# zap.net
KiCad netlist of a schematic drawn in EAGLE
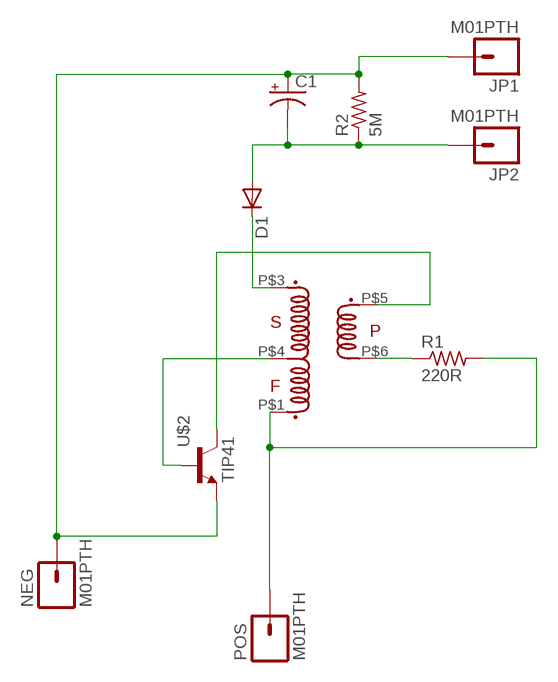
[diagram p0: schematic, sheet 1]

(export (version "E")
  (design (tool "Eeschema 10.0.6"))
  (components
    (comp (ref "C1")
      (value "CAPACITOR_POL")
      (footprint "eagle-import:E5-10,5-SIDE")
      (libsource (lib "eagle-import") (part "CAPACITOR_POL"))
    )
    (comp (ref "D1")
      (value "DIODEPTH")
      (footprint "eagle-import:DIODE-1N4001")
      (libsource (lib "eagle-import") (part "DIODEPTH"))
    )
    (comp (ref "JP1")
      (value "M01PTH")
      (footprint "eagle-import:1X01")
      (libsource (lib "eagle-import") (part "M01PTH"))
    )
    (comp (ref "JP2")
      (value "M01PTH")
      (footprint "eagle-import:1X01")
      (libsource (lib "eagle-import") (part "M01PTH"))
    )
    (comp (ref "NEG")
      (value "M01PTH")
      (footprint "eagle-import:1X01")
      (libsource (lib "eagle-import") (part "M01PTH"))
    )
    (comp (ref "POS")
      (value "M01PTH")
      (footprint "eagle-import:1X01")
      (libsource (lib "eagle-import") (part "M01PTH"))
    )
    (comp (ref "R1")
      (value "220R")
      (footprint "eagle-import:0207_12")
      (libsource (lib "eagle-import") (part "RESISTOR0207/12"))
    )
    (comp (ref "R2")
      (value "5M")
      (footprint "eagle-import:0207_7")
      (libsource (lib "eagle-import") (part "RESISTOR0207/7"))
    )
    (comp (ref "U$1")
      (value "XFT-FLYBACK3V")
      (footprint "eagle-import:XFT-FLYBACK")
      (libsource (lib "eagle-import") (part "XFT-FLYBACK3V"))
    )
    (comp (ref "U$2")
      (value "TIP41")
      (footprint "eagle-import:TO220H")
      (libsource (lib "eagle-import") (part "TIP41"))
    )
  )
  (nets
    (net (code "1") (name "Net-(C1-+)") (class "Default")
      (node (ref "C1") (pin "P$1") (pinfunction "+_P$1") (pintype "passive"))
      (node (ref "JP1") (pin "1") (pinfunction "1_1") (pintype "passive"))
      (node (ref "NEG") (pin "1") (pinfunction "1_1") (pintype "passive"))
      (node (ref "R2") (pin "2") (pinfunction "2_2") (pintype "passive"))
      (node (ref "U$2") (pin "3") (pinfunction "E_3") (pintype "passive"))
    )
    (net (code "2") (name "Net-(C1--)") (class "Default")
      (node (ref "C1") (pin "P$2") (pinfunction "-_P$2") (pintype "passive"))
      (node (ref "D1") (pin "A") (pinfunction "A_A") (pintype "passive"))
      (node (ref "JP2") (pin "1") (pinfunction "1_1") (pintype "passive"))
      (node (ref "R2") (pin "1") (pinfunction "1_1") (pintype "passive"))
    )
    (net (code "3") (name "Net-(U$1-P$1.S)") (class "Default")
      (node (ref "D1") (pin "C") (pinfunction "C_C") (pintype "passive"))
      (node (ref "U$1") (pin "P$3") (pinfunction "P$1.S_P$3") (pintype "passive"))
    )
    (net (code "4") (name "Net-(U$1-P$2.CENTRE)") (class "Default")
      (node (ref "U$1") (pin "P$4") (pinfunction "P$2.CENTRE_P$4") (pintype "passive"))
      (node (ref "U$2") (pin "1") (pinfunction "B_1") (pintype "passive"))
    )
    (net (code "5") (name "Net-(U$1-P$3.F)") (class "Default")
      (node (ref "POS") (pin "1") (pinfunction "1_1") (pintype "passive"))
      (node (ref "R1") (pin "2") (pinfunction "2_2") (pintype "passive"))
      (node (ref "U$1") (pin "P$1") (pinfunction "P$3.F_P$1") (pintype "passive"))
    )
    (net (code "6") (name "Net-(U$1-P$4.P1)") (class "Default")
      (node (ref "U$1") (pin "P$5") (pinfunction "P$4.P1_P$5") (pintype "passive"))
      (node (ref "U$2") (pin "2") (pinfunction "C_2") (pintype "passive"))
    )
    (net (code "7") (name "Net-(U$1-P$5.P2)") (class "Default")
      (node (ref "R1") (pin "1") (pinfunction "1_1") (pintype "passive"))
      (node (ref "U$1") (pin "P$6") (pinfunction "P$5.P2_P$6") (pintype "passive"))
    )
  )
)
